# Charlotte5822_32-Channel-Wireless-Headst.net
KiCad netlist of a schematic drawn in Altium Designer
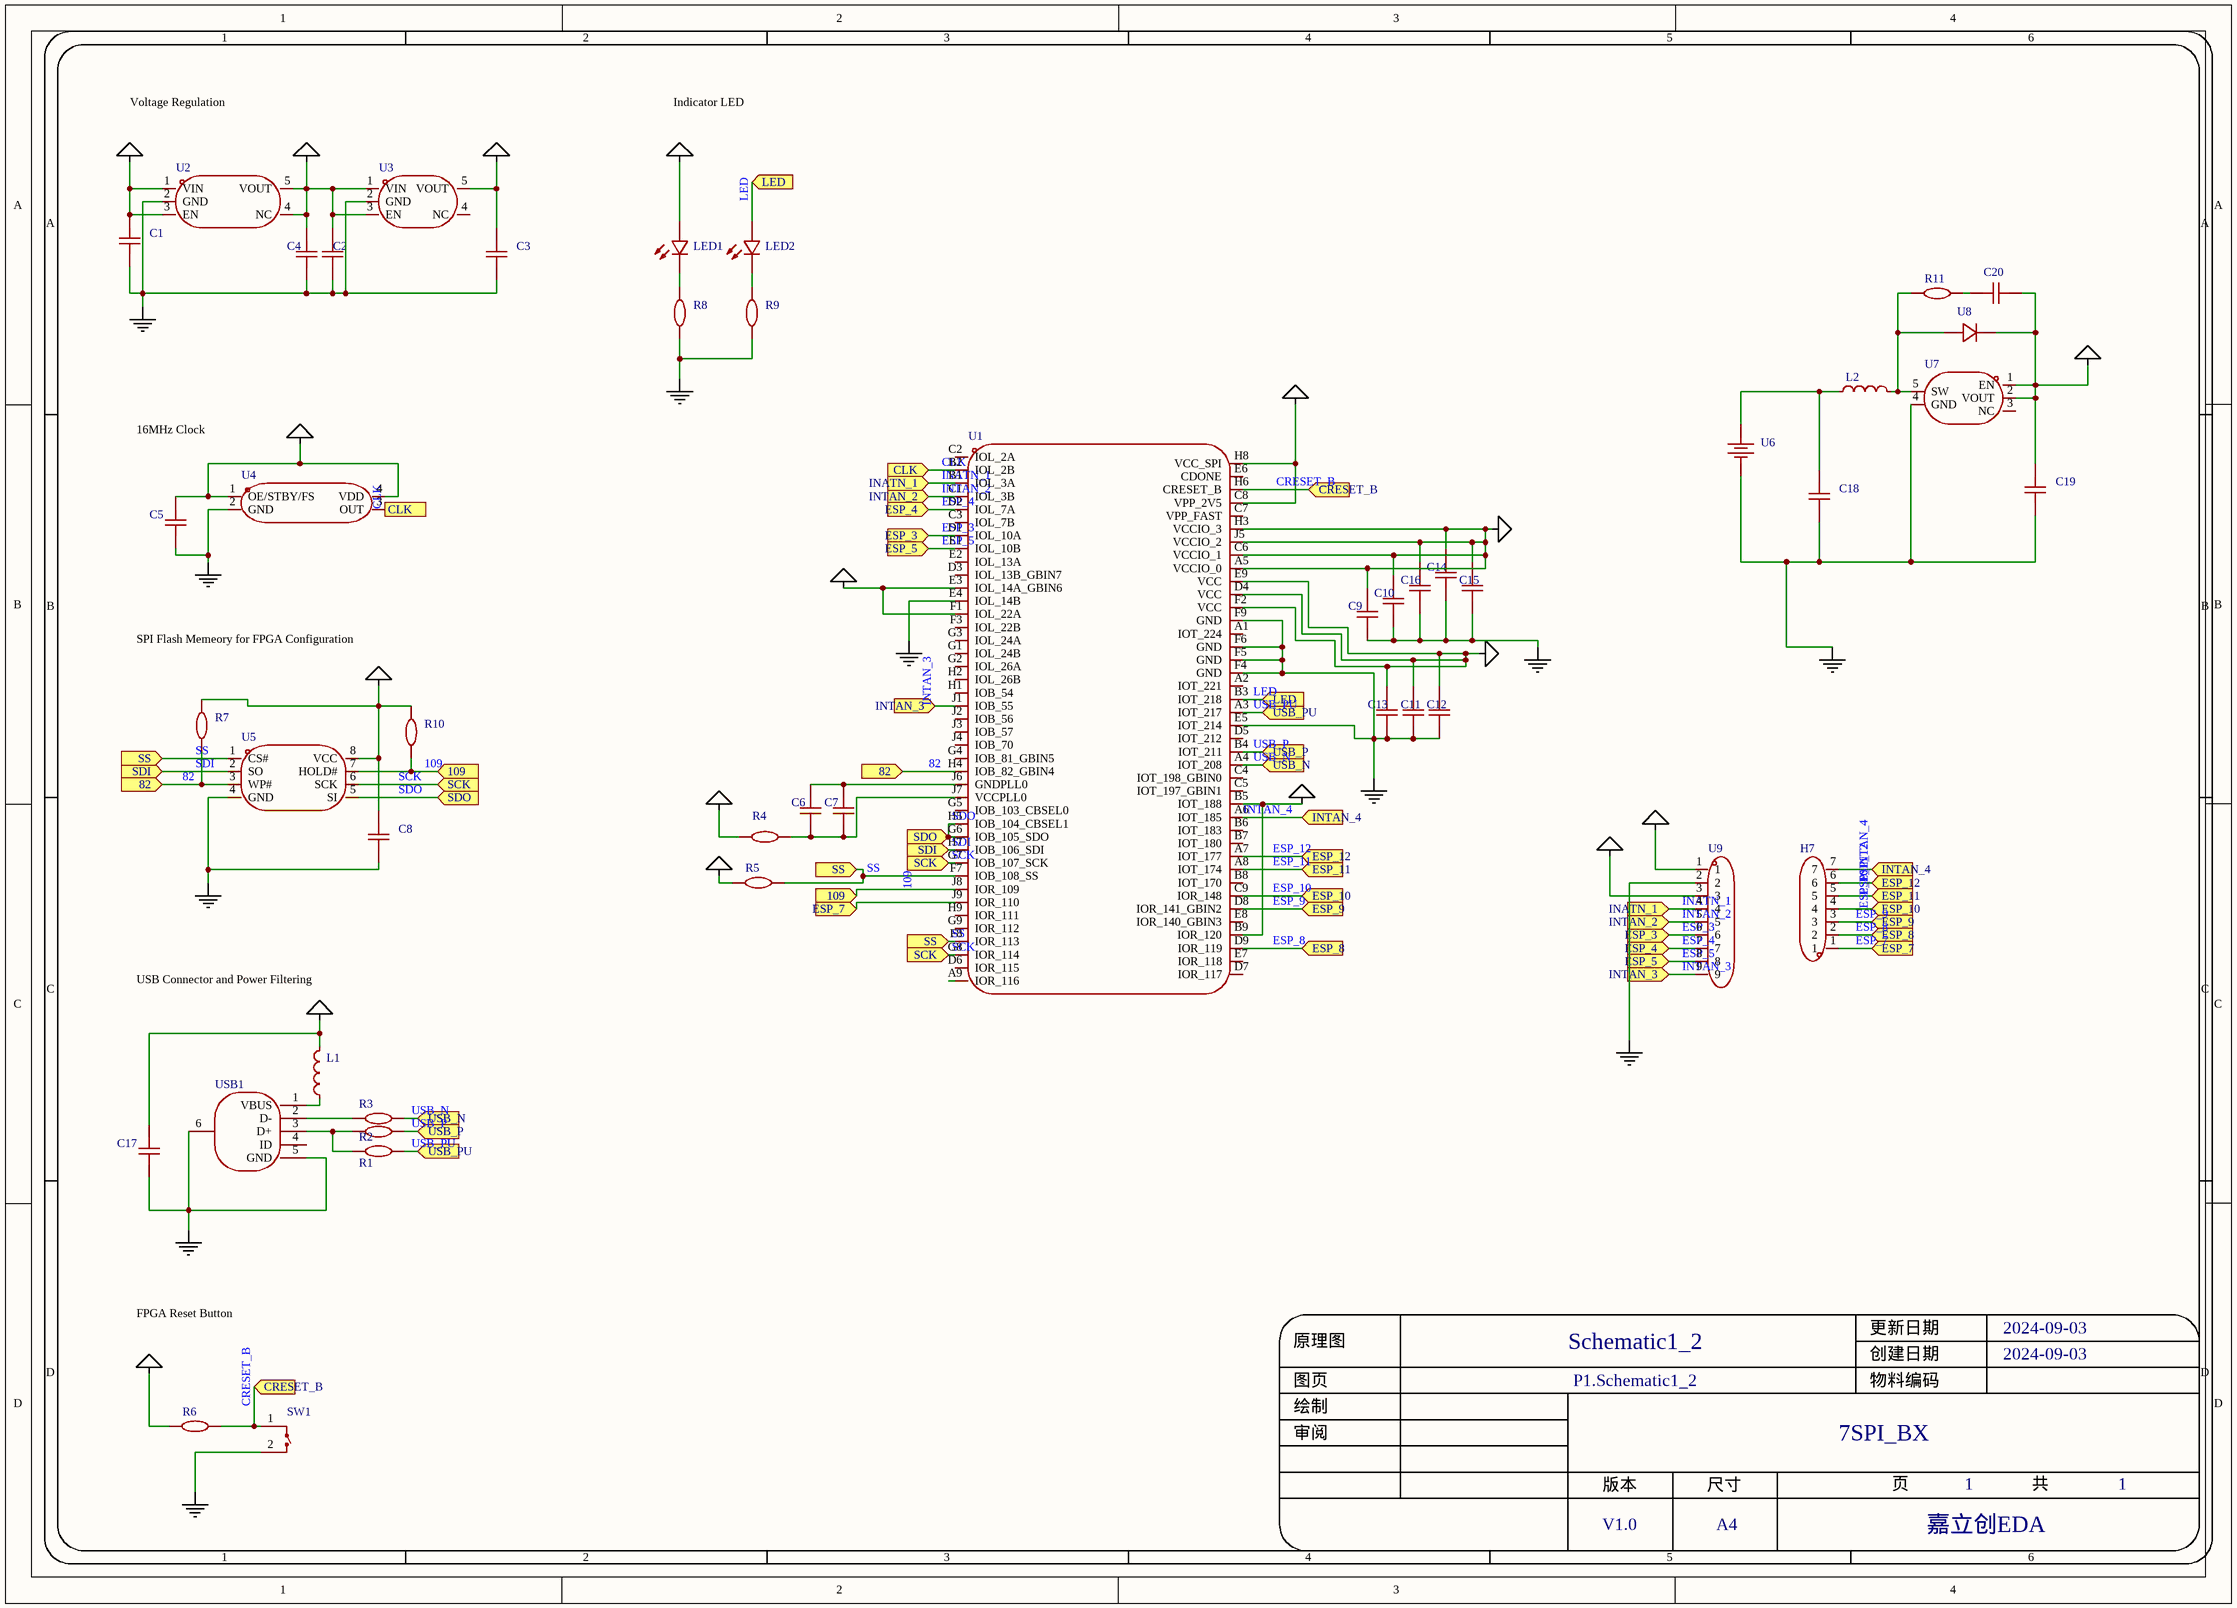
[diagram p0: Charlotte5822_32-Channel-Wireless-Headstage__PCB_AltiumDesigner_FPGA_iCEStick_Schematic1_2__1_P1.schdoc]

(export (version "E")
  (design (tool "Eeschema 10.0.6"))
  (components
    (comp (ref "C1")
      (value "1uF")
      (footprint "C0201")
      (description "容值:1uF;精度:±20%;额定电压:16V;材质(温度系数):X5R;")
      (fields
        (field (name "MANUFACTURER") "muRata(村田)")
        (field (name "MANUFACTURER PART") "GRM033R61C105ME15D")
      )
      (libsource (lib "altium-import") (part "root_1_GRM033R61C105ME15D_"))
    )
    (comp (ref "C2")
      (value "1uF")
      (footprint "C0201")
      (description "容值:1uF;精度:±20%;额定电压:16V;材质(温度系数):X5R;")
      (fields
        (field (name "MANUFACTURER") "muRata(村田)")
        (field (name "MANUFACTURER PART") "GRM033R61C105ME15D")
      )
      (libsource (lib "altium-import") (part "root_1_GRM033R61C105ME15D_"))
    )
    (comp (ref "C3")
      (value "1uF")
      (footprint "C0201")
      (description "容值:1uF;精度:±20%;额定电压:16V;材质(温度系数):X5R;")
      (fields
        (field (name "MANUFACTURER") "muRata(村田)")
        (field (name "MANUFACTURER PART") "GRM033R61C105ME15D")
      )
      (libsource (lib "altium-import") (part "root_1_GRM033R61C105ME15D_"))
    )
    (comp (ref "C4")
      (value "1uF")
      (footprint "C0201")
      (description "容值:1uF;精度:±20%;额定电压:16V;材质(温度系数):X5R;")
      (fields
        (field (name "MANUFACTURER") "muRata(村田)")
        (field (name "MANUFACTURER PART") "GRM033R61C105ME15D")
      )
      (libsource (lib "altium-import") (part "root_1_GRM033R61C105ME15D_"))
    )
    (comp (ref "C5")
      (value "100nF")
      (footprint "C0201")
      (description "容值:100nF;精度:±10%;额定电压:25V;材质(温度系数):X5R;")
      (fields
        (field (name "MANUFACTURER") "muRata(村田)")
        (field (name "MANUFACTURER PART") "GRM033R61E104KE14D")
      )
      (libsource (lib "altium-import") (part "root_1_GRM033R61E104KE14D_"))
    )
    (comp (ref "C6")
      (value "10uF")
      (footprint "C0402")
      (description "容值:10uF;精度:±20%;额定电压:6.3V;材质(温度系数):X5R;")
      (fields
        (field (name "MANUFACTURER") "SAMSUNG(三星)")
        (field (name "MANUFACTURER PART") "CL05A106MQ5NUNC")
      )
      (libsource (lib "altium-import") (part "root_1_CL05A106MQ5NUNC_"))
    )
    (comp (ref "C7")
      (value "100nF")
      (footprint "C0201")
      (description "容值:100nF;精度:±10%;额定电压:25V;材质(温度系数):X5R;")
      (fields
        (field (name "MANUFACTURER") "muRata(村田)")
        (field (name "MANUFACTURER PART") "GRM033R61E104KE14D")
      )
      (libsource (lib "altium-import") (part "root_1_GRM033R61E104KE14D_"))
    )
    (comp (ref "C8")
      (value "100nF")
      (footprint "C0201")
      (description "容值:100nF;精度:±10%;额定电压:25V;材质(温度系数):X5R;")
      (fields
        (field (name "MANUFACTURER") "muRata(村田)")
        (field (name "MANUFACTURER PART") "GRM033R61E104KE14D")
      )
      (libsource (lib "altium-import") (part "root_1_GRM033R61E104KE14D_"))
    )
    (comp (ref "C9")
      (value "100nF")
      (footprint "C0201")
      (description "容值:100nF;精度:±10%;额定电压:25V;材质(温度系数):X5R;")
      (fields
        (field (name "MANUFACTURER") "muRata(村田)")
        (field (name "MANUFACTURER PART") "GRM033R61E104KE14D")
      )
      (libsource (lib "altium-import") (part "root_1_GRM033R61E104KE14D_"))
    )
    (comp (ref "C10")
      (value "100nF")
      (footprint "C0201")
      (description "容值:100nF;精度:±10%;额定电压:25V;材质(温度系数):X5R;")
      (fields
        (field (name "MANUFACTURER") "muRata(村田)")
        (field (name "MANUFACTURER PART") "GRM033R61E104KE14D")
      )
      (libsource (lib "altium-import") (part "root_1_GRM033R61E104KE14D_"))
    )
    (comp (ref "C11")
      (value "100nF")
      (footprint "C0201")
      (description "容值:100nF;精度:±10%;额定电压:25V;材质(温度系数):X5R;")
      (fields
        (field (name "MANUFACTURER") "muRata(村田)")
        (field (name "MANUFACTURER PART") "GRM033R61E104KE14D")
      )
      (libsource (lib "altium-import") (part "root_1_GRM033R61E104KE14D_"))
    )
    (comp (ref "C12")
      (value "10nF")
      (footprint "C0201")
      (description "容值:10nF;精度:±10%;额定电压:10V;材质(温度系数):X7R;")
      (fields
        (field (name "MANUFACTURER") "muRata(村田)")
        (field (name "MANUFACTURER PART") "GRM033R71A103KA01D")
      )
      (libsource (lib "altium-import") (part "root_1_GRM033R71A103KA01D_"))
    )
    (comp (ref "C13")
      (value "10nF")
      (footprint "C0201")
      (description "容值:10nF;精度:±10%;额定电压:10V;材质(温度系数):X7R;")
      (fields
        (field (name "MANUFACTURER") "muRata(村田)")
        (field (name "MANUFACTURER PART") "GRM033R71A103KA01D")
      )
      (libsource (lib "altium-import") (part "root_1_GRM033R71A103KA01D_"))
    )
    (comp (ref "C14")
      (value "10nF")
      (footprint "C0201")
      (description "容值:100nF;精度:±10%;额定电压:25V;材质(温度系数):X5R;")
      (fields
        (field (name "MANUFACTURER") "muRata(村田)")
        (field (name "MANUFACTURER PART") "GRM033R61E104KE14D")
      )
      (libsource (lib "altium-import") (part "root_1_GRM033R61E104KE14D_"))
    )
    (comp (ref "C15")
      (value "10nF")
      (footprint "C0201")
      (description "容值:10nF;精度:±10%;额定电压:10V;材质(温度系数):X7R;")
      (fields
        (field (name "MANUFACTURER") "muRata(村田)")
        (field (name "MANUFACTURER PART") "GRM033R71A103KA01D")
      )
      (libsource (lib "altium-import") (part "root_1_GRM033R71A103KA01D_"))
    )
    (comp (ref "C16")
      (value "100nF")
      (footprint "C0201")
      (description "容值:100nF;精度:±10%;额定电压:25V;材质(温度系数):X5R;")
      (fields
        (field (name "MANUFACTURER") "muRata(村田)")
        (field (name "MANUFACTURER PART") "GRM033R61E104KE14D")
      )
      (libsource (lib "altium-import") (part "root_1_GRM033R61E104KE14D_"))
    )
    (comp (ref "C17")
      (value "10uF")
      (footprint "C0402")
      (description "容值:10uF;精度:±20%;额定电压:6.3V;材质(温度系数):X5R;")
      (fields
        (field (name "MANUFACTURER") "SAMSUNG(三星)")
        (field (name "MANUFACTURER PART") "CL05A106MQ5NUNC")
      )
      (libsource (lib "altium-import") (part "root_1_CL05A106MQ5NUNC_"))
    )
    (comp (ref "C18")
      (value "100nF")
      (footprint "C0402")
      (description "容值:100nF;精度:±10%;额定电压:16V;材质(温度系数):X7R;")
      (fields
        (field (name "MANUFACTURER") "YAGEO(国巨)")
        (field (name "MANUFACTURER PART") "CC0402KRX7R7BB104")
      )
      (libsource (lib "altium-import") (part "root_1_CC0402KRX7R7BB104_"))
    )
    (comp (ref "C19")
      (value "22uF")
      (footprint "C0402")
      (description "容值:22uF;精度:±20%;额定电压:6.3V;材质(温度系数):X5R;")
      (fields
        (field (name "MANUFACTURER") "SAMSUNG(三星)")
        (field (name "MANUFACTURER PART") "CL05A226MQ5QUNC")
      )
      (libsource (lib "altium-import") (part "root_1_CL05A226MQ5QUNC_"))
    )
    (comp (ref "C20")
      (value "4.7uF")
      (footprint "C0402")
      (description "容值:4.7uF;精度:±20%;额定电压:10V;材质(温度系数):X5R;")
      (fields
        (field (name "MANUFACTURER") "SAMSUNG(三星)")
        (field (name "MANUFACTURER PART") "CL05A475MP5NRNC")
      )
      (libsource (lib "altium-import") (part "root_0_CL05A475MP5NRNC_"))
    )
    (comp (ref "H7")
      (value "PZ254V-11-07P")
      (footprint "HDR-TH_7P-P2.54-V-M")
      (fields (field (name "MANUFACTURER") "XFCN(兴飞)"))
      (libsource (lib "altium-import") (part "root_2_PZ254V-11-07P_"))
    )
    (comp (ref "L1")
      (value "3.3uH")
      (footprint "L0603")
      (description "电感值:3.3uH;精度:±10%;额定电流:15mA;饱和电流(Isat):-;直流电阻(DCR):1.55Ω;")
      (fields
        (field (name "MANUFACTURER") "Sunltech(韩国顺磁)")
        (field (name "MANUFACTURER PART") "SCL1608Q3R3KSP")
      )
      (libsource (lib "altium-import") (part "root_1_SCL1608Q3R3KSP_"))
    )
    (comp (ref "L2")
      (value "3.3uH")
      (footprint "L0603")
      (description "电感值:3.3uH;精度:±10%;额定电流:15mA;饱和电流(Isat):-;直流电阻(DCR):1Ω;")
      (fields (field (name "MANUFACTURER") "FH(风华)") (field (name "MANUFACTURER PART") "CMI160808U3R3KT"))
      (libsource (lib "altium-import") (part "root_0_CMI160808U3R3KT_"))
    )
    (comp (ref "LED1")
      (value "NCD0603R1")
      (footprint "LED0603-RD_RED")
      (fields (field (name "MANUFACTURER") "国星光电"))
      (libsource (lib "altium-import") (part "root_1_NCD0603R1_C84263_"))
    )
    (comp (ref "LED2")
      (value "NCD0603R1")
      (footprint "LED0603-RD_RED")
      (fields (field (name "MANUFACTURER") "国星光电"))
      (libsource (lib "altium-import") (part "root_1_NCD0603R1_C84263_"))
    )
    (comp (ref "R1")
      (value "1.5kΩ")
      (footprint "R0201")
      (description "电阻类型:厚膜电阻;阻值:1.5kΩ;精度:±1%;功率:50mW;最大工作电压:25V;温度系数:±200ppm/℃;")
      (fields
        (field (name "MANUFACTURER") "UNI-ROYAL(厚声)")
        (field (name "MANUFACTURER PART") "0201WMF1501TEE")
      )
      (libsource (lib "altium-import") (part "root_0_0201WMF1501TEE_"))
    )
    (comp (ref "R2")
      (value "68Ω")
      (footprint "R0201")
      (description "电阻类型:厚膜电阻;阻值:68Ω;精度:±1%;功率:50mW;最大工作电压:-;温度系数:±200ppm/℃;")
      (fields (field (name "MANUFACTURER") "KOA") (field (name "MANUFACTURER PART") "RK73H1HTTC68R0F"))
      (libsource (lib "altium-import") (part "root_0_RK73H1HTTC68R0F_"))
    )
    (comp (ref "R3")
      (value "68Ω")
      (footprint "R0201")
      (description "电阻类型:厚膜电阻;阻值:68Ω;精度:±1%;功率:50mW;最大工作电压:-;温度系数:±200ppm/℃;")
      (fields (field (name "MANUFACTURER") "KOA") (field (name "MANUFACTURER PART") "RK73H1HTTC68R0F"))
      (libsource (lib "altium-import") (part "root_0_RK73H1HTTC68R0F_"))
    )
    (comp (ref "R4")
      (value "100Ω")
      (footprint "R0201")
      (description "电阻类型:厚膜电阻;阻值:100Ω;精度:±1%;功率:50mW;最大工作电压:25V;温度系数:±200ppm/℃;")
      (fields (field (name "MANUFACTURER") "YAGEO(国巨)") (field (name "MANUFACTURER PART") "RC0201FR-07100RL"))
      (libsource (lib "altium-import") (part "root_0_RC0201FR-07100RL_"))
    )
    (comp (ref "R5")
      (value "10kΩ")
      (footprint "R0201")
      (description "电阻类型:厚膜电阻;阻值:10kΩ;精度:±1%;功率:50mW;最大工作电压:25V;温度系数:±200ppm/℃;")
      (fields
        (field (name "MANUFACTURER") "UNI-ROYAL(厚声)")
        (field (name "MANUFACTURER PART") "0201WMF1002TEE")
      )
      (libsource (lib "altium-import") (part "root_0_0201WMF1002TEE_"))
    )
    (comp (ref "R6")
      (value "4.7kΩ")
      (footprint "R0201")
      (description "电阻类型:厚膜电阻;阻值:4.7kΩ;精度:±1%;功率:50mW;最大工作电压:25V;温度系数:±200ppm/℃;")
      (fields
        (field (name "MANUFACTURER") "UNI-ROYAL(厚声)")
        (field (name "MANUFACTURER PART") "0201WMF4701TEE")
      )
      (libsource (lib "altium-import") (part "root_0_0201WMF4701TEE_"))
    )
    (comp (ref "R7")
      (value "10kΩ")
      (footprint "R0201")
      (description "电阻类型:厚膜电阻;阻值:10kΩ;精度:±1%;功率:50mW;最大工作电压:25V;温度系数:±200ppm/℃;")
      (fields
        (field (name "MANUFACTURER") "UNI-ROYAL(厚声)")
        (field (name "MANUFACTURER PART") "0201WMF1002TEE")
      )
      (libsource (lib "altium-import") (part "root_1_0201WMF1002TEE_"))
    )
    (comp (ref "R8")
      (value "270Ω")
      (footprint "R0201")
      (description "电阻类型:厚膜电阻;阻值:270Ω;精度:±1%;功率:50mW;最大工作电压:25V;温度系数:±200ppm/℃;")
      (fields
        (field (name "MANUFACTURER") "UNI-ROYAL(厚声)")
        (field (name "MANUFACTURER PART") "0201WMF2700TEE")
      )
      (libsource (lib "altium-import") (part "root_1_0201WMF2700TEE_"))
    )
    (comp (ref "R9")
      (value "270Ω")
      (footprint "R0201")
      (description "电阻类型:厚膜电阻;阻值:270Ω;精度:±1%;功率:50mW;最大工作电压:25V;温度系数:±200ppm/℃;")
      (fields
        (field (name "MANUFACTURER") "UNI-ROYAL(厚声)")
        (field (name "MANUFACTURER PART") "0201WMF2700TEE")
      )
      (libsource (lib "altium-import") (part "root_1_0201WMF2700TEE_"))
    )
    (comp (ref "R10")
      (value "10kΩ")
      (footprint "R0201")
      (description "电阻类型:厚膜电阻;阻值:10kΩ;精度:±1%;功率:50mW;最大工作电压:25V;温度系数:±200ppm/℃;")
      (fields
        (field (name "MANUFACTURER") "UNI-ROYAL(厚声)")
        (field (name "MANUFACTURER PART") "0201WMF1002TEE")
      )
      (libsource (lib "altium-import") (part "root_1_0201WMF1002TEE_"))
    )
    (comp (ref "R11")
      (value "10kΩ")
      (footprint "R0402")
      (description "电阻类型:厚膜电阻;阻值:10kΩ;精度:±1%;功率:62.5mW;最大工作电压:50V;温度系数:±100ppm/℃;")
      (fields (field (name "MANUFACTURER") "YAGEO(国巨)") (field (name "MANUFACTURER PART") "RC0402FR-0710KL"))
      (libsource (lib "altium-import") (part "root_0_RC0402FR-0710KL_"))
    )
    (comp (ref "SW1")
      (value "TS-3025-A-A-B")
      (footprint "SW-SMD_L3.0-W2.5-P3.40-LS4.0-L")
      (fields (field (name "MANUFACTURER") "XKB Connectivity(中国星坤)"))
      (libsource (lib "altium-import") (part "root_0_TS-3025-A-A-B_"))
    )
    (comp (ref "U1")
      (value "ICE40LP8K-CM81")
      (footprint "ice40_spec")
      (description "类型:-;逻辑门数量:-;逻辑单元数:7680;逻辑阵列块数:960;")
      (fields (field (name "MANUFACTURER") "LATTICE(莱迪思)"))
      (libsource (lib "altium-import") (part "root_0_ICE40LP8K-CM81_"))
    )
    (comp (ref "U2")
      (value "MIC5504-3.3YM5-TR")
      (footprint "SOT-23-5_L3.0-W1.7-P0.95-LS2.8-TL")
      (description "输出类型:固定;最大输入电压:5.5V;输出电压:3.3V;最大输出电流:300mA;电源纹波抑制比(PSRR):60dB@(1kHz);输出极性:正极;")
      (fields (field (name "MANUFACTURER") "MICROCHIP(美国微芯)"))
      (libsource (lib "altium-import") (part "root_0_MIC5504-3.3YM5-TR_"))
    )
    (comp (ref "U3")
      (value "MIC5365-1.2YC5-TR")
      (footprint "SC-70-5_L2.1-W1.3-P0.65-LS2.1-BL")
      (description "输出类型:固定;最大输入电压:5.5V;输出电压:1.2V;最大输出电流:150mA;电源纹波抑制比(PSRR):80dB;输出极性:正极;")
      (fields (field (name "MANUFACTURER") "MICROCHIP(美国微芯)"))
      (libsource (lib "altium-import") (part "root_0_MIC5365-1.2YC5-TR_"))
    )
    (comp (ref "U4")
      (value "DSC6001CI2A-016.0000")
      (footprint "OSC-SMD_4P-L3.2-W2.5-BL_DSC1001CL5")
      (fields (field (name "MANUFACTURER") "MICROCHIP(美国微芯)"))
      (libsource (lib "altium-import") (part "root_0_DSC6001CI2A-016.0000_"))
    )
    (comp (ref "U5")
      (value "AT25SF081-SSHD-B")
      (footprint "SOP-8_L4.9-W3.9-P1.27-LS6.0-BL")
      (fields (field (name "MANUFACTURER") "Dialog/Adesto"))
      (libsource (lib "altium-import") (part "root_0_AT25SF081-SSHD-B_"))
    )
    (comp (ref "U6")
      (value "MS621FE-FL11E")
      (footprint "BAT-SMD_FL11E")
      (description "FL11E 3.3V可充电纽扣电池 5.5mAH")
      (fields (field (name "MANUFACTURER") "Seiko(精工)") (field (name "VOLTAGE") "3 V"))
      (libsource (lib "altium-import") (part "root_3_MS621FE-FL11E_"))
    )
    (comp (ref "U7")
      (value "PW5100-50")
      (footprint "SOT-23-5_L2.9-W1.6-P0.95-LS2.8-BL")
      (libsource (lib "altium-import") (part "root_0_mirrored_PW5100-50_"))
    )
    (comp (ref "U8")
      (value "CD4148WSP")
      (footprint "D0805-RD")
      (description "二极管配置:-;正向压降(Vf):1.25V@100mA;直流反向耐压(Vr):75V;平均整流电流(Io):150mA;功率:400mW;反向恢复时间(trr):4ns;")
      (fields (field (name "MANUFACTURER") "LIZ(丽智电子)"))
      (libsource (lib "altium-import") (part "root_2_CD4148WSP_"))
    )
    (comp (ref "U9")
      (value "PM254-1-09-Z-8.5")
      (footprint "HDR-TH_9P-P2.54-V-F")
      (fields (field (name "MANUFACTURER") "HCTL(华灿天禄)"))
      (libsource (lib "altium-import") (part "root_0_PM254-1-09-Z-8.5_"))
    )
    (comp (ref "USB1")
      (value "MICRO QTZB5.0")
      (footprint "MICRO-USB-SMD_MICRO-QTZB5.0")
      (description "连接器类型:Micro-B;标准:USB 2.0;公母:母;端口数量:1;触点数量:5P;安装方式:卧贴;额定电流 - 电源:1A;工作温度范围:-30℃~+80℃;")
      (fields (field (name "MANUFACTURER") "SHOU HAN(首韩)"))
      (libsource (lib "altium-import") (part "root_0_MICRO QTZB5.0_"))
    )
  )
  (nets
    (net (code "1") (name "+1V2") (class "Default")
      (node (ref "C11") (pin "2") (pinfunction "2_2") (pintype "passive"))
      (node (ref "C12") (pin "2") (pinfunction "2_2") (pintype "passive"))
      (node (ref "C13") (pin "2") (pinfunction "2_2") (pintype "passive"))
      (node (ref "C3") (pin "2") (pinfunction "2_2") (pintype "passive"))
      (node (ref "R4") (pin "1") (pinfunction "1_1") (pintype "passive"))
      (node (ref "U1") (pin "D4") (pinfunction "VCC_D4") (pintype "passive"))
      (node (ref "U1") (pin "E3") (pinfunction "IOL_14A_GBIN6_E3") (pintype "passive"))
      (node (ref "U1") (pin "E9") (pinfunction "VCC_E9") (pintype "passive"))
      (node (ref "U1") (pin "F1") (pinfunction "IOL_22A_F1") (pintype "passive"))
      (node (ref "U1") (pin "F2") (pinfunction "VCC_F2") (pintype "passive"))
      (node (ref "U3") (pin "5") (pinfunction "VOUT_5") (pintype "passive"))
    )
    (net (code "2") (name "+3V3") (class "Default")
      (node (ref "C10") (pin "2") (pinfunction "2_2") (pintype "passive"))
      (node (ref "C14") (pin "2") (pinfunction "2_2") (pintype "passive"))
      (node (ref "C15") (pin "2") (pinfunction "2_2") (pintype "passive"))
      (node (ref "C16") (pin "2") (pinfunction "2_2") (pintype "passive"))
      (node (ref "C2") (pin "2") (pinfunction "2_2") (pintype "passive"))
      (node (ref "C4") (pin "2") (pinfunction "2_2") (pintype "passive"))
      (node (ref "C5") (pin "2") (pinfunction "2_2") (pintype "passive"))
      (node (ref "C8") (pin "2") (pinfunction "2_2") (pintype "passive"))
      (node (ref "C9") (pin "2") (pinfunction "2_2") (pintype "passive"))
      (node (ref "LED1") (pin "2") (pinfunction "A_2") (pintype "passive"))
      (node (ref "R10") (pin "2") (pinfunction "2_2") (pintype "passive"))
      (node (ref "R5") (pin "1") (pinfunction "1_1") (pintype "passive"))
      (node (ref "R6") (pin "1") (pinfunction "1_1") (pintype "passive"))
      (node (ref "R7") (pin "2") (pinfunction "2_2") (pintype "passive"))
      (node (ref "U1") (pin "A5") (pinfunction "VCCIO_0_A5") (pintype "passive"))
      (node (ref "U1") (pin "B5") (pinfunction "IOT_188_B5") (pintype "passive"))
      (node (ref "U1") (pin "B9") (pinfunction "IOR_120_B9") (pintype "passive"))
      (node (ref "U1") (pin "C6") (pinfunction "VCCIO_1_C6") (pintype "passive"))
      (node (ref "U1") (pin "C8") (pinfunction "VPP_2V5_C8") (pintype "passive"))
      (node (ref "U1") (pin "H3") (pinfunction "VCCIO_3_H3") (pintype "passive"))
      (node (ref "U1") (pin "H8") (pinfunction "VCC_SPI_H8") (pintype "passive"))
      (node (ref "U1") (pin "J5") (pinfunction "VCCIO_2_J5") (pintype "passive"))
      (node (ref "U2") (pin "4") (pinfunction "NC_4") (pintype "passive"))
      (node (ref "U2") (pin "5") (pinfunction "VOUT_5") (pintype "passive"))
      (node (ref "U3") (pin "1") (pinfunction "VIN_1") (pintype "passive"))
      (node (ref "U3") (pin "3") (pinfunction "EN_3") (pintype "passive"))
      (node (ref "U4") (pin "1") (pinfunction "OE/STBY/FS_1") (pintype "passive"))
      (node (ref "U4") (pin "4") (pinfunction "VDD_4") (pintype "passive"))
      (node (ref "U5") (pin "8") (pinfunction "VCC_8") (pintype "passive"))
      (node (ref "U9") (pin "3") (pinfunction "3_3") (pintype "passive"))
    )
    (net (code "3") (name "+5V") (class "Default")
      (node (ref "C1") (pin "2") (pinfunction "2_2") (pintype "passive"))
      (node (ref "C17") (pin "2") (pinfunction "2_2") (pintype "passive"))
      (node (ref "C19") (pin "2") (pinfunction "2_2") (pintype "passive"))
      (node (ref "C20") (pin "2") (pinfunction "2_2") (pintype "passive"))
      (node (ref "L1") (pin "2") (pinfunction "2_2") (pintype "passive"))
      (node (ref "U2") (pin "1") (pinfunction "VIN_1") (pintype "passive"))
      (node (ref "U2") (pin "3") (pinfunction "EN_3") (pintype "passive"))
      (node (ref "U7") (pin "1") (pinfunction "EN_1") (pintype "passive"))
      (node (ref "U7") (pin "2") (pinfunction "VOUT_2") (pintype "passive"))
      (node (ref "U8") (pin "1") (pinfunction "K_1") (pintype "passive"))
      (node (ref "U9") (pin "1") (pinfunction "1_1") (pintype "passive"))
    )
    (net (code "4") (name "/82") (class "Default")
      (node (ref "R7") (pin "1") (pinfunction "1_1") (pintype "passive"))
      (node (ref "U1") (pin "H4") (pinfunction "IOB_82_GBIN4_H4") (pintype "passive"))
      (node (ref "U5") (pin "3") (pinfunction "WP#_3") (pintype "passive"))
    )
    (net (code "5") (name "/109") (class "Default")
      (node (ref "R10") (pin "1") (pinfunction "1_1") (pintype "passive"))
      (node (ref "U1") (pin "J8") (pinfunction "IOR_109_J8") (pintype "passive"))
      (node (ref "U5") (pin "7") (pinfunction "HOLD#_7") (pintype "passive"))
    )
    (net (code "6") (name "/CLK") (class "Default")
      (node (ref "U1") (pin "B2") (pinfunction "IOL_2B_B2") (pintype "passive"))
      (node (ref "U4") (pin "3") (pinfunction "OUT_3") (pintype "passive"))
    )
    (net (code "7") (name "/CRESET_B") (class "Default")
      (node (ref "R6") (pin "2") (pinfunction "2_2") (pintype "passive"))
      (node (ref "SW1") (pin "1") (pinfunction "1_1") (pintype "passive"))
      (node (ref "U1") (pin "H6") (pinfunction "CRESET_B_H6") (pintype "passive"))
    )
    (net (code "8") (name "/ESP_3") (class "Default")
      (node (ref "U1") (pin "D1") (pinfunction "IOL_10A_D1") (pintype "passive"))
      (node (ref "U9") (pin "6") (pinfunction "6_6") (pintype "passive"))
    )
    (net (code "9") (name "/ESP_4") (class "Default")
      (node (ref "U1") (pin "D2") (pinfunction "IOL_7A_D2") (pintype "passive"))
      (node (ref "U9") (pin "7") (pinfunction "7_7") (pintype "passive"))
    )
    (net (code "10") (name "/ESP_5") (class "Default")
      (node (ref "U1") (pin "E1") (pinfunction "IOL_10B_E1") (pintype "passive"))
      (node (ref "U9") (pin "8") (pinfunction "8_8") (pintype "passive"))
    )
    (net (code "11") (name "/ESP_7") (class "Default")
      (node (ref "H7") (pin "1") (pinfunction "1_1") (pintype "passive"))
      (node (ref "U1") (pin "J9") (pinfunction "IOR_110_J9") (pintype "passive"))
    )
    (net (code "12") (name "/ESP_8") (class "Default")
      (node (ref "H7") (pin "2") (pinfunction "2_2") (pintype "passive"))
      (node (ref "U1") (pin "D9") (pinfunction "IOR_119_D9") (pintype "passive"))
    )
    (net (code "13") (name "/ESP_9") (class "Default")
      (node (ref "H7") (pin "3") (pinfunction "3_3") (pintype "passive"))
      (node (ref "U1") (pin "D8") (pinfunction "IOR_141_GBIN2_D8") (pintype "passive"))
    )
    (net (code "14") (name "/ESP_10") (class "Default")
      (node (ref "H7") (pin "4") (pinfunction "4_4") (pintype "passive"))
      (node (ref "U1") (pin "C9") (pinfunction "IOR_148_C9") (pintype "passive"))
    )
    (net (code "15") (name "/ESP_11") (class "Default")
      (node (ref "H7") (pin "5") (pinfunction "5_5") (pintype "passive"))
      (node (ref "U1") (pin "A8") (pinfunction "IOT_174_A8") (pintype "passive"))
    )
    (net (code "16") (name "/ESP_12") (class "Default")
      (node (ref "H7") (pin "6") (pinfunction "6_6") (pintype "passive"))
      (node (ref "U1") (pin "A7") (pinfunction "IOT_177_A7") (pintype "passive"))
    )
    (net (code "17") (name "/INATN_1") (class "Default")
      (node (ref "U1") (pin "B1") (pinfunction "IOL_3A_B1") (pintype "passive"))
      (node (ref "U9") (pin "4") (pinfunction "4_4") (pintype "passive"))
    )
    (net (code "18") (name "/INTAN_2") (class "Default")
      (node (ref "U1") (pin "C1") (pinfunction "IOL_3B_C1") (pintype "passive"))
      (node (ref "U9") (pin "5") (pinfunction "5_5") (pintype "passive"))
    )
    (net (code "19") (name "/INTAN_3") (class "Default")
      (node (ref "U1") (pin "J1") (pinfunction "IOB_55_J1") (pintype "passive"))
      (node (ref "U9") (pin "9") (pinfunction "9_9") (pintype "passive"))
    )
    (net (code "20") (name "/INTAN_4") (class "Default")
      (node (ref "H7") (pin "7") (pinfunction "7_7") (pintype "passive"))
      (node (ref "U1") (pin "A6") (pinfunction "IOT_185_A6") (pintype "passive"))
    )
    (net (code "21") (name "/LED") (class "Default")
      (node (ref "LED2") (pin "2") (pinfunction "A_2") (pintype "passive"))
      (node (ref "U1") (pin "B3") (pinfunction "IOT_218_B3") (pintype "passive"))
    )
    (net (code "22") (name "/SCK") (class "Default")
      (node (ref "U1") (pin "G7") (pinfunction "IOB_107_SCK_G7") (pintype "passive"))
      (node (ref "U1") (pin "G8") (pinfunction "IOR_114_G8") (pintype "passive"))
      (node (ref "U5") (pin "6") (pinfunction "SCK_6") (pintype "passive"))
    )
    (net (code "23") (name "/SDI") (class "Default")
      (node (ref "U1") (pin "H7") (pinfunction "IOB_106_SDI_H7") (pintype "passive"))
      (node (ref "U5") (pin "2") (pinfunction "SO_2") (pintype "passive"))
    )
    (net (code "24") (name "/SDO") (class "Default")
      (node (ref "U1") (pin "G6") (pinfunction "IOB_105_SDO_G6") (pintype "passive"))
      (node (ref "U1") (pin "H5") (pinfunction "IOB_104_CBSEL1_H5") (pintype "passive"))
      (node (ref "U5") (pin "5") (pinfunction "SI_5") (pintype "passive"))
    )
    (net (code "25") (name "/SS") (class "Default")
      (node (ref "R5") (pin "2") (pinfunction "2_2") (pintype "passive"))
      (node (ref "U1") (pin "F7") (pinfunction "IOB_108_SS_F7") (pintype "passive"))
      (node (ref "U1") (pin "F8") (pinfunction "IOR_113_F8") (pintype "passive"))
      (node (ref "U5") (pin "1") (pinfunction "CS#_1") (pintype "passive"))
    )
    (net (code "26") (name "/USB_N") (class "Default")
      (node (ref "R3") (pin "2") (pinfunction "2_2") (pintype "passive"))
      (node (ref "U1") (pin "A4") (pinfunction "IOT_208_A4") (pintype "passive"))
    )
    (net (code "27") (name "/USB_P") (class "Default")
      (node (ref "R2") (pin "2") (pinfunction "2_2") (pintype "passive"))
      (node (ref "U1") (pin "B4") (pinfunction "IOT_211_B4") (pintype "passive"))
    )
    (net (code "28") (name "/USB_PU") (class "Default")
      (node (ref "R1") (pin "2") (pinfunction "2_2") (pintype "passive"))
      (node (ref "U1") (pin "A3") (pinfunction "IOT_217_A3") (pintype "passive"))
    )
    (net (code "29") (name "GND") (class "Default")
      (node (ref "C1") (pin "1") (pinfunction "1_1") (pintype "passive"))
      (node (ref "C10") (pin "1") (pinfunction "1_1") (pintype "passive"))
      (node (ref "C11") (pin "1") (pinfunction "1_1") (pintype "passive"))
      (node (ref "C12") (pin "1") (pinfunction "1_1") (pintype "passive"))
      (node (ref "C13") (pin "1") (pinfunction "1_1") (pintype "passive"))
      (node (ref "C14") (pin "1") (pinfunction "1_1") (pintype "passive"))
      (node (ref "C15") (pin "1") (pinfunction "1_1") (pintype "passive"))
      (node (ref "C16") (pin "1") (pinfunction "1_1") (pintype "passive"))
      (node (ref "C17") (pin "1") (pinfunction "1_1") (pintype "passive"))
      (node (ref "C18") (pin "1") (pinfunction "1_1") (pintype "passive"))
      (node (ref "C19") (pin "1") (pinfunction "1_1") (pintype "passive"))
      (node (ref "C2") (pin "1") (pinfunction "1_1") (pintype "passive"))
      (node (ref "C3") (pin "1") (pinfunction "1_1") (pintype "passive"))
      (node (ref "C4") (pin "1") (pinfunction "1_1") (pintype "passive"))
      (node (ref "C5") (pin "1") (pinfunction "1_1") (pintype "passive"))
      (node (ref "C8") (pin "1") (pinfunction "1_1") (pintype "passive"))
      (node (ref "C9") (pin "1") (pinfunction "1_1") (pintype "passive"))
      (node (ref "R8") (pin "1") (pinfunction "1_1") (pintype "passive"))
      (node (ref "R9") (pin "1") (pinfunction "1_1") (pintype "passive"))
      (node (ref "SW1") (pin "2") (pinfunction "2_2") (pintype "passive"))
      (node (ref "U1") (pin "E4") (pinfunction "IOL_14B_E4") (pintype "passive"))
      (node (ref "U1") (pin "E5") (pinfunction "IOT_214_E5") (pintype "passive"))
      (node (ref "U1") (pin "F4") (pinfunction "GND_F4") (pintype "passive"))
      (node (ref "U1") (pin "F5") (pinfunction "GND_F5") (pintype "passive"))
      (node (ref "U1") (pin "F6") (pinfunction "GND_F6") (pintype "passive"))
      (node (ref "U1") (pin "F9") (pinfunction "GND_F9") (pintype "passive"))
      (node (ref "U2") (pin "2") (pinfunction "GND_2") (pintype "passive"))
      (node (ref "U3") (pin "2") (pinfunction "GND_2") (pintype "passive"))
      (node (ref "U4") (pin "2") (pinfunction "GND_2") (pintype "passive"))
      (node (ref "U5") (pin "4") (pinfunction "GND_4") (pintype "passive"))
      (node (ref "U6") (pin "2") (pinfunction "-_2") (pintype "passive"))
      (node (ref "U7") (pin "4") (pinfunction "GND_4") (pintype "passive"))
      (node (ref "U9") (pin "2") (pinfunction "2_2") (pintype "passive"))
      (node (ref "USB1") (pin "5") (pinfunction "GND_5") (pintype "passive"))
      (node (ref "USB1") (pin "6") (pinfunction "EH_6") (pintype "passive"))
    )
    (net (code "30") (name "Net-(C20-Pad1)") (class "Default")
      (node (ref "C20") (pin "1") (pinfunction "1_1") (pintype "passive"))
      (node (ref "R11") (pin "2") (pinfunction "2_2") (pintype "passive"))
    )
    (net (code "31") (name "Net-(LED1-K)") (class "Default")
      (node (ref "LED1") (pin "1") (pinfunction "K_1") (pintype "passive"))
      (node (ref "R8") (pin "2") (pinfunction "2_2") (pintype "passive"))
    )
    (net (code "32") (name "Net-(LED2-K)") (class "Default")
      (node (ref "LED2") (pin "1") (pinfunction "K_1") (pintype "passive"))
      (node (ref "R9") (pin "2") (pinfunction "2_2") (pintype "passive"))
    )
    (net (code "33") (name "Net-(U1-GNDPLL0)") (class "Default")
      (node (ref "C6") (pin "2") (pinfunction "2_2") (pintype "passive"))
      (node (ref "C7") (pin "2") (pinfunction "2_2") (pintype "passive"))
      (node (ref "U1") (pin "J6") (pinfunction "GNDPLL0_J6") (pintype "passive"))
    )
    (net (code "34") (name "Net-(U1-VCCPLL0)") (class "Default")
      (node (ref "C6") (pin "1") (pinfunction "1_1") (pintype "passive"))
      (node (ref "C7") (pin "1") (pinfunction "1_1") (pintype "passive"))
      (node (ref "R4") (pin "2") (pinfunction "2_2") (pintype "passive"))
      (node (ref "U1") (pin "J7") (pinfunction "VCCPLL0_J7") (pintype "passive"))
    )
    (net (code "35") (name "Net-(U6-+)") (class "Default")
      (node (ref "C18") (pin "2") (pinfunction "2_2") (pintype "passive"))
      (node (ref "L2") (pin "1") (pinfunction "1_1") (pintype "passive"))
      (node (ref "U6") (pin "1") (pinfunction "+_1") (pintype "passive"))
    )
    (net (code "36") (name "Net-(U7-SW)") (class "Default")
      (node (ref "L2") (pin "2") (pinfunction "2_2") (pintype "passive"))
      (node (ref "R11") (pin "1") (pinfunction "1_1") (pintype "passive"))
      (node (ref "U7") (pin "5") (pinfunction "SW_5") (pintype "passive"))
      (node (ref "U8") (pin "2") (pinfunction "A_2") (pintype "passive"))
    )
    (net (code "37") (name "Net-(USB1-D+)") (class "Default")
      (node (ref "R1") (pin "1") (pinfunction "1_1") (pintype "passive"))
      (node (ref "R2") (pin "1") (pinfunction "1_1") (pintype "passive"))
      (node (ref "USB1") (pin "3") (pinfunction "D+_3") (pintype "passive"))
    )
    (net (code "38") (name "Net-(USB1-D-)") (class "Default")
      (node (ref "R3") (pin "1") (pinfunction "1_1") (pintype "passive"))
      (node (ref "USB1") (pin "2") (pinfunction "D-_2") (pintype "passive"))
    )
    (net (code "39") (name "Net-(USB1-VBUS)") (class "Default")
      (node (ref "L1") (pin "1") (pinfunction "1_1") (pintype "passive"))
      (node (ref "USB1") (pin "1") (pinfunction "VBUS_1") (pintype "passive"))
    )
    (net (code "40") (name "unconnected-(U1-CDONE-PadE6)") (class "Default")
      (node (ref "U1") (pin "E6") (pinfunction "CDONE_E6") (pintype "passive"))
    )
    (net (code "41") (name "unconnected-(U1-IOB_54-PadH1)") (class "Default")
      (node (ref "U1") (pin "H1") (pinfunction "IOB_54_H1") (pintype "passive"))
    )
    (net (code "42") (name "unconnected-(U1-IOB_56-PadJ2)") (class "Default")
      (node (ref "U1") (pin "J2") (pinfunction "IOB_56_J2") (pintype "passive"))
    )
    (net (code "43") (name "unconnected-(U1-IOB_57-PadJ3)") (class "Default")
      (node (ref "U1") (pin "J3") (pinfunction "IOB_57_J3") (pintype "passive"))
    )
    (net (code "44") (name "unconnected-(U1-IOB_70-PadJ4)") (class "Default")
      (node (ref "U1") (pin "J4") (pinfunction "IOB_70_J4") (pintype "passive"))
    )
    (net (code "45") (name "unconnected-(U1-IOB_81_GBIN5-PadG4)") (class "Default")
      (node (ref "U1") (pin "G4") (pinfunction "IOB_81_GBIN5_G4") (pintype "passive"))
    )
    (net (code "46") (name "unconnected-(U1-IOB_103_CBSEL0-PadG5)") (class "Default")
      (node (ref "U1") (pin "G5") (pinfunction "IOB_103_CBSEL0_G5") (pintype "passive"))
    )
    (net (code "47") (name "unconnected-(U1-IOL_2A-PadC2)") (class "Default")
      (node (ref "U1") (pin "C2") (pinfunction "IOL_2A_C2") (pintype "passive"))
    )
    (net (code "48") (name "unconnected-(U1-IOL_7B-PadC3)") (class "Default")
      (node (ref "U1") (pin "C3") (pinfunction "IOL_7B_C3") (pintype "passive"))
    )
    (net (code "49") (name "unconnected-(U1-IOL_13A-PadE2)") (class "Default")
      (node (ref "U1") (pin "E2") (pinfunction "IOL_13A_E2") (pintype "passive"))
    )
    (net (code "50") (name "unconnected-(U1-IOL_13B_GBIN7-PadD3)") (class "Default")
      (node (ref "U1") (pin "D3") (pinfunction "IOL_13B_GBIN7_D3") (pintype "passive"))
    )
    (net (code "51") (name "unconnected-(U1-IOL_22B-PadF3)") (class "Default")
      (node (ref "U1") (pin "F3") (pinfunction "IOL_22B_F3") (pintype "passive"))
    )
    (net (code "52") (name "unconnected-(U1-IOL_24A-PadG3)") (class "Default")
      (node (ref "U1") (pin "G3") (pinfunction "IOL_24A_G3") (pintype "passive"))
    )
    (net (code "53") (name "unconnected-(U1-IOL_24B-PadG1)") (class "Default")
      (node (ref "U1") (pin "G1") (pinfunction "IOL_24B_G1") (pintype "passive"))
    )
    (net (code "54") (name "unconnected-(U1-IOL_26A-PadG2)") (class "Default")
      (node (ref "U1") (pin "G2") (pinfunction "IOL_26A_G2") (pintype "passive"))
    )
    (net (code "55") (name "unconnected-(U1-IOL_26B-PadH2)") (class "Default")
      (node (ref "U1") (pin "H2") (pinfunction "IOL_26B_H2") (pintype "passive"))
    )
    (net (code "56") (name "unconnected-(U1-IOR_111-PadH9)") (class "Default")
      (node (ref "U1") (pin "H9") (pinfunction "IOR_111_H9") (pintype "passive"))
    )
    (net (code "57") (name "unconnected-(U1-IOR_112-PadG9)") (class "Default")
      (node (ref "U1") (pin "G9") (pinfunction "IOR_112_G9") (pintype "passive"))
    )
    (net (code "58") (name "unconnected-(U1-IOR_115-PadD6)") (class "Default")
      (node (ref "U1") (pin "D6") (pinfunction "IOR_115_D6") (pintype "passive"))
    )
    (net (code "59") (name "unconnected-(U1-IOR_116-PadA9)") (class "Default")
      (node (ref "U1") (pin "A9") (pinfunction "IOR_116_A9") (pintype "passive"))
    )
    (net (code "60") (name "unconnected-(U1-IOR_117-PadD7)") (class "Default")
      (node (ref "U1") (pin "D7") (pinfunction "IOR_117_D7") (pintype "passive"))
    )
    (net (code "61") (name "unconnected-(U1-IOR_118-PadE7)") (class "Default")
      (node (ref "U1") (pin "E7") (pinfunction "IOR_118_E7") (pintype "passive"))
    )
    (net (code "62") (name "unconnected-(U1-IOR_140_GBIN3-PadE8)") (class "Default")
      (node (ref "U1") (pin "E8") (pinfunction "IOR_140_GBIN3_E8") (pintype "passive"))
    )
    (net (code "63") (name "unconnected-(U1-IOT_170-PadB8)") (class "Default")
      (node (ref "U1") (pin "B8") (pinfunction "IOT_170_B8") (pintype "passive"))
    )
    (net (code "64") (name "unconnected-(U1-IOT_180-PadB7)") (class "Default")
      (node (ref "U1") (pin "B7") (pinfunction "IOT_180_B7") (pintype "passive"))
    )
    (net (code "65") (name "unconnected-(U1-IOT_183-PadB6)") (class "Default")
      (node (ref "U1") (pin "B6") (pinfunction "IOT_183_B6") (pintype "passive"))
    )
    (net (code "66") (name "unconnected-(U1-IOT_197_GBIN1-PadC5)") (class "Default")
      (node (ref "U1") (pin "C5") (pinfunction "IOT_197_GBIN1_C5") (pintype "passive"))
    )
    (net (code "67") (name "unconnected-(U1-IOT_198_GBIN0-PadC4)") (class "Default")
      (node (ref "U1") (pin "C4") (pinfunction "IOT_198_GBIN0_C4") (pintype "passive"))
    )
    (net (code "68") (name "unconnected-(U1-IOT_212-PadD5)") (class "Default")
      (node (ref "U1") (pin "D5") (pinfunction "IOT_212_D5") (pintype "passive"))
    )
    (net (code "69") (name "unconnected-(U1-IOT_221-PadA2)") (class "Default")
      (node (ref "U1") (pin "A2") (pinfunction "IOT_221_A2") (pintype "passive"))
    )
    (net (code "70") (name "unconnected-(U1-IOT_224-PadA1)") (class "Default")
      (node (ref "U1") (pin "A1") (pinfunction "IOT_224_A1") (pintype "passive"))
    )
    (net (code "71") (name "unconnected-(U1-VPP_FAST-PadC7)") (class "Default")
      (node (ref "U1") (pin "C7") (pinfunction "VPP_FAST_C7") (pintype "passive"))
    )
    (net (code "72") (name "unconnected-(U3-NC-Pad4)") (class "Default")
      (node (ref "U3") (pin "4") (pinfunction "NC_4") (pintype "passive"))
    )
    (net (code "73") (name "unconnected-(U7-NC-Pad3)") (class "Default")
      (node (ref "U7") (pin "3") (pinfunction "NC_3") (pintype "passive"))
    )
    (net (code "74") (name "unconnected-(USB1-ID-Pad4)") (class "Default")
      (node (ref "USB1") (pin "4") (pinfunction "ID_4") (pintype "passive"))
    )
  )
)
